# WSTL18_UART.net
KiCad netlist of a schematic drawn in EAGLE
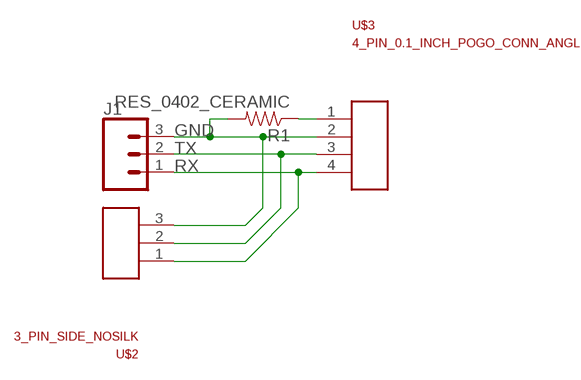
[diagram p0: schematic, sheet 1]

(export (version "E")
  (design (tool "Eeschema 10.0.6"))
  (components
    (comp (ref "J1")
      (value "CONN_03")
      (footprint "eagle-import:1X03")
      (libsource (lib "eagle-import") (part "CONN_03"))
    )
    (comp (ref "R1")
      (value "RES_0402_CERAMIC")
      (footprint "eagle-import:RES_0402")
      (libsource (lib "eagle-import") (part "RES_0402_CERAMIC"))
    )
    (comp (ref "U$2")
      (value "3_PIN_SIDE_NOSILK")
      (footprint "eagle-import:3PIN_SIDE_0.1_INCH_NOSILK")
      (libsource (lib "eagle-import") (part "3_PIN_SIDE_NOSILK"))
    )
    (comp (ref "U$3")
      (value "4_PIN_0.1_INCH_POGO_CONN_ANGLE")
      (footprint "eagle-import:4_PIN_0.1INCH_POGO_PADS_ANGLE")
      (libsource (lib "eagle-import") (part "4_PIN_0.1_INCH_POGO_CONN_ANGLE"))
    )
  )
  (nets
    (net (code "1") (name "/GND") (class "Default")
      (node (ref "J1") (pin "3") (pinfunction "3_3") (pintype "passive"))
      (node (ref "R1") (pin "1") (pinfunction "1_1") (pintype "passive"))
      (node (ref "U$2") (pin "3") (pinfunction "3_3") (pintype "bidirectional"))
      (node (ref "U$3") (pin "2") (pinfunction "2_2") (pintype "bidirectional"))
    )
    (net (code "2") (name "/RX") (class "Default")
      (node (ref "J1") (pin "1") (pinfunction "1_1") (pintype "passive"))
      (node (ref "U$2") (pin "1") (pinfunction "1_1") (pintype "bidirectional"))
      (node (ref "U$3") (pin "4") (pinfunction "4_4") (pintype "bidirectional"))
    )
    (net (code "3") (name "/TX") (class "Default")
      (node (ref "J1") (pin "2") (pinfunction "2_2") (pintype "passive"))
      (node (ref "U$2") (pin "2") (pinfunction "2_2") (pintype "bidirectional"))
      (node (ref "U$3") (pin "3") (pinfunction "3_3") (pintype "bidirectional"))
    )
    (net (code "4") (name "Net-(R1-Pad2)") (class "Default")
      (node (ref "R1") (pin "2") (pinfunction "2_2") (pintype "passive"))
      (node (ref "U$3") (pin "1") (pinfunction "1_1") (pintype "bidirectional"))
    )
  )
)
